# Insight.net
KiCad netlist of a schematic drawn in EAGLE
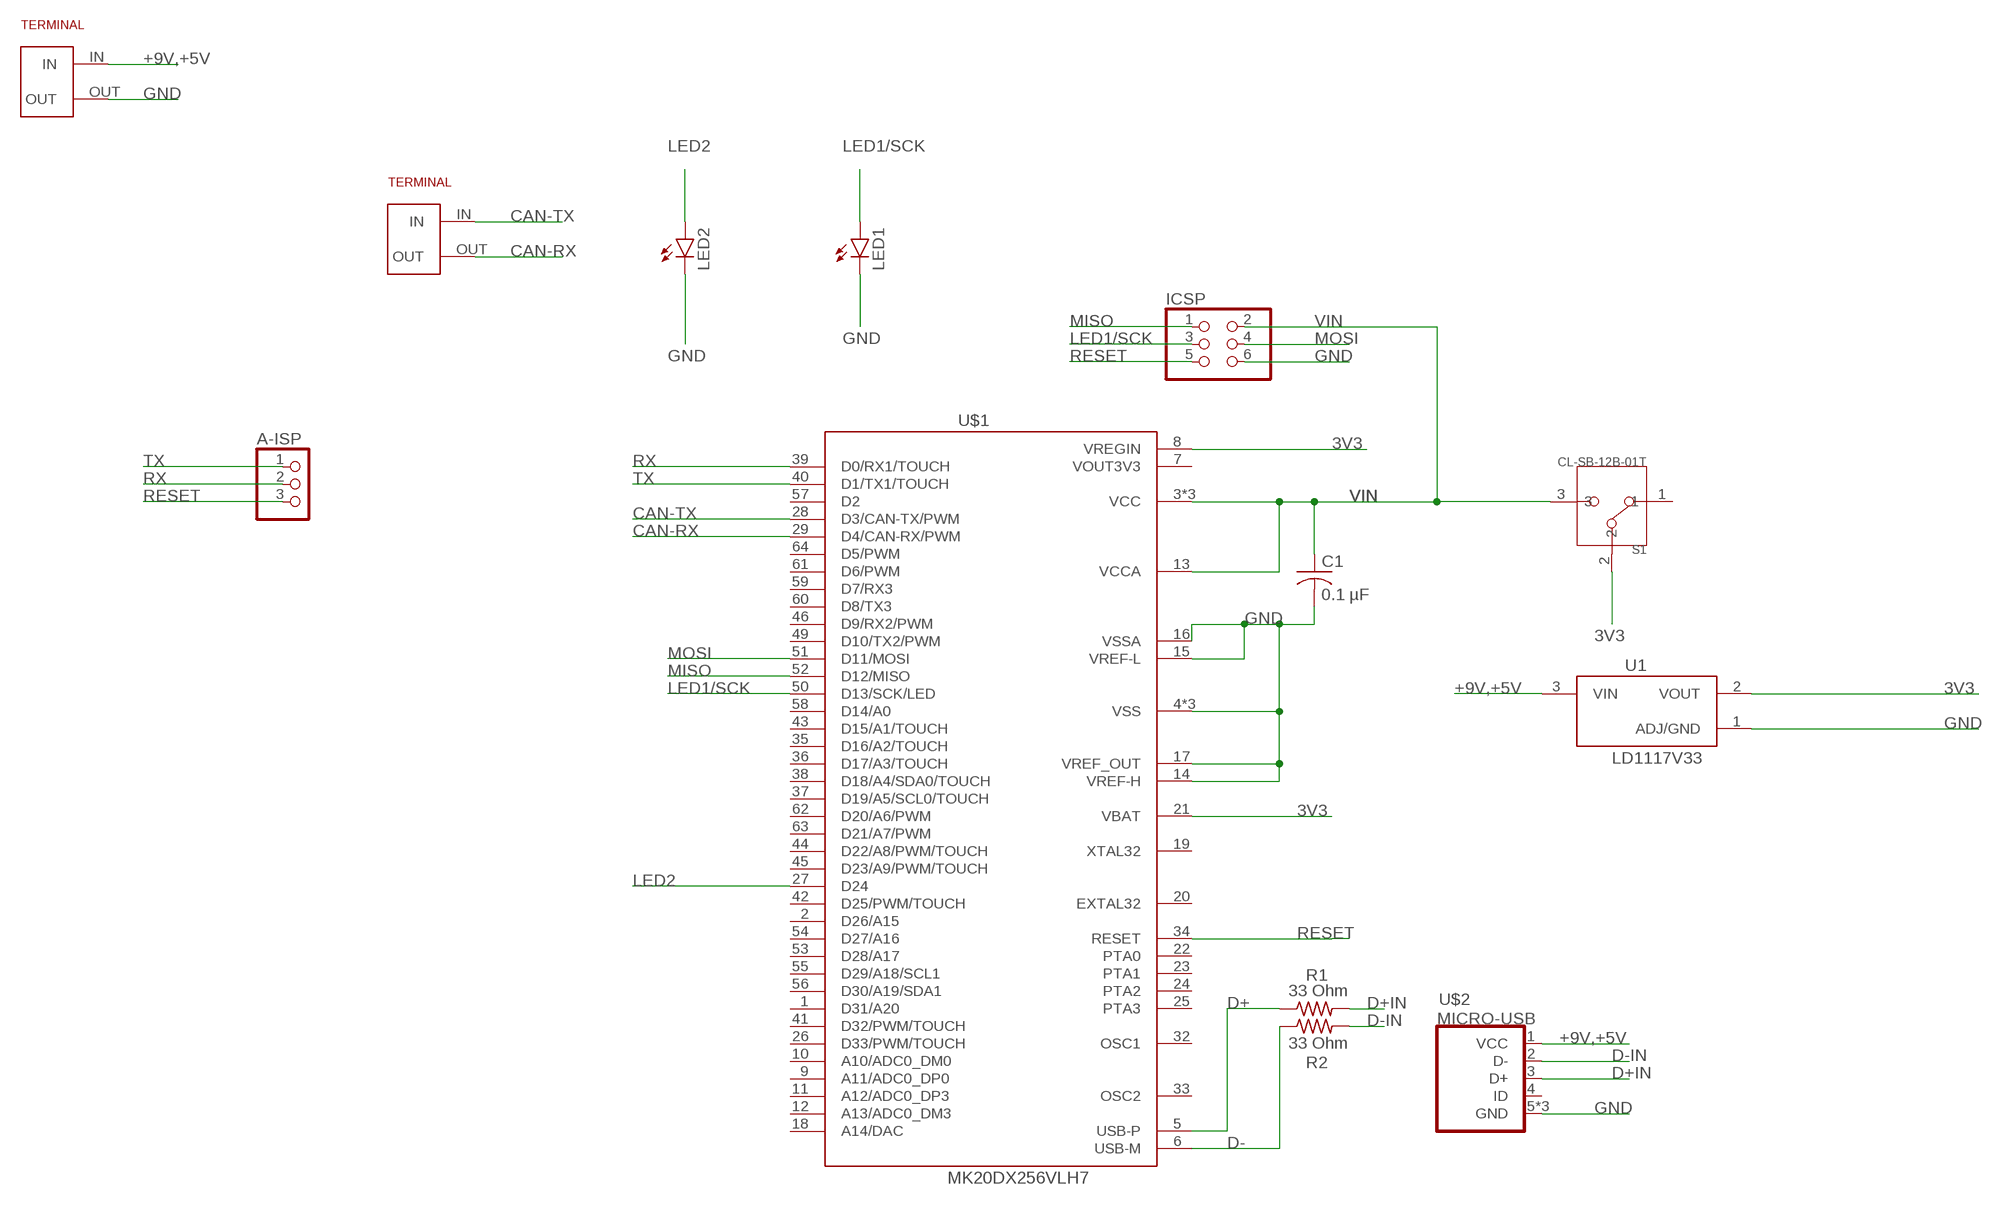
[diagram p0: schematic, sheet 1]

(export (version "E")
  (design (tool "Eeschema 10.0.6"))
  (components
    (comp (ref "A-ISP")
      (value "PINHD-1X3")
      (footprint "eagle-import:1X03")
      (libsource (lib "eagle-import") (part "PINHD-1X3"))
    )
    (comp (ref "C1")
      (value "0.1 µF")
      (footprint "eagle-import:C0805")
      (libsource (lib "eagle-import") (part "C-USC0805"))
    )
    (comp (ref "ICSP")
      (value "PINHD-2X3")
      (footprint "eagle-import:2X03")
      (libsource (lib "eagle-import") (part "PINHD-2X3"))
    )
    (comp (ref "LED1")
      (value "LED5MM")
      (footprint "eagle-import:LED5MM")
      (libsource (lib "eagle-import") (part "LED5MM"))
    )
    (comp (ref "LED2")
      (value "LED5MM")
      (footprint "eagle-import:LED5MM")
      (libsource (lib "eagle-import") (part "LED5MM"))
    )
    (comp (ref "R1")
      (value "33 Ohm")
      (footprint "eagle-import:R1206")
      (libsource (lib "eagle-import") (part "R-US_R1206"))
    )
    (comp (ref "R2")
      (value "33 Ohm")
      (footprint "eagle-import:R1206")
      (libsource (lib "eagle-import") (part "R-US_R1206"))
    )
    (comp (ref "S1")
      (value "CL-SB-12B-01T")
      (footprint "eagle-import:CL-SB-12B")
      (fields (field (name "MF") "Nidec Copal"))
      (libsource (lib "eagle-import") (part "CL-SB-12B-01T"))
    )
    (comp (ref "U$1")
      (value "MK20DX256VLH7")
      (footprint "eagle-import:QFP50P1200X1200X160-64N")
      (fields (field (name "MF") "NXP USA"))
      (libsource (lib "eagle-import") (part "MK20DX256VLH7"))
    )
    (comp (ref "U$2")
      (value "MICRO-USB")
      (footprint "eagle-import:MICRO-USB")
      (libsource (lib "eagle-import") (part "MICRO-USB"))
    )
    (comp (ref "U$3")
      (value "SCREWTERMINAL")
      (footprint "eagle-import:SCREWTERMINAL")
      (libsource (lib "eagle-import") (part "SCREWTERMINAL"))
    )
    (comp (ref "U$4")
      (value "SCREWTERMINAL")
      (footprint "eagle-import:SCREWTERMINAL")
      (libsource (lib "eagle-import") (part "SCREWTERMINAL"))
    )
    (comp (ref "U1")
      (value "LD1117V33")
      (footprint "eagle-import:TO255P1020X450X1968-3")
      (fields (field (name "MF") "STMicroelectronics"))
      (libsource (lib "eagle-import") (part "LD1117V33"))
    )
  )
  (nets
    (net (code "1") (name "/+9V,+5V") (class "Default")
      (node (ref "U$2") (pin "1") (pinfunction "VCC_1") (pintype "power_in"))
      (node (ref "U$3") (pin "IN") (pinfunction "IN_IN") (pintype "bidirectional"))
      (node (ref "U1") (pin "3") (pinfunction "VIN_3") (pintype "input"))
    )
    (net (code "2") (name "/3V3") (class "Default")
      (node (ref "S1") (pin "2") (pinfunction "2_2") (pintype "bidirectional"))
      (node (ref "U$1") (pin "21") (pinfunction "VBAT_21") (pintype "bidirectional"))
      (node (ref "U$1") (pin "8") (pinfunction "VREGIN_8") (pintype "bidirectional"))
      (node (ref "U1") (pin "2") (pinfunction "VOUT_2") (pintype "output"))
    )
    (net (code "3") (name "/CAN-RX") (class "Default")
      (node (ref "U$1") (pin "29") (pinfunction "D4/CAN-RX/PWM_29") (pintype "bidirectional"))
      (node (ref "U$4") (pin "OUT") (pinfunction "OUT_OUT") (pintype "bidirectional"))
    )
    (net (code "4") (name "/CAN-TX") (class "Default")
      (node (ref "U$1") (pin "28") (pinfunction "D3/CAN-TX/PWM_28") (pintype "bidirectional"))
      (node (ref "U$4") (pin "IN") (pinfunction "IN_IN") (pintype "bidirectional"))
    )
    (net (code "5") (name "/D+") (class "Default")
      (node (ref "R1") (pin "1") (pinfunction "1_1") (pintype "passive"))
      (node (ref "U$1") (pin "5") (pinfunction "USB-P_5") (pintype "bidirectional"))
    )
    (net (code "6") (name "/D+IN") (class "Default")
      (node (ref "R1") (pin "2") (pinfunction "2_2") (pintype "passive"))
      (node (ref "U$2") (pin "3") (pinfunction "D+_3") (pintype "bidirectional"))
    )
    (net (code "7") (name "/D-") (class "Default")
      (node (ref "R2") (pin "1") (pinfunction "1_1") (pintype "passive"))
      (node (ref "U$1") (pin "6") (pinfunction "USB-M_6") (pintype "bidirectional"))
    )
    (net (code "8") (name "/D-IN") (class "Default")
      (node (ref "R2") (pin "2") (pinfunction "2_2") (pintype "passive"))
      (node (ref "U$2") (pin "2") (pinfunction "D-_2") (pintype "bidirectional"))
    )
    (net (code "9") (name "/GND") (class "Default")
      (node (ref "C1") (pin "2") (pinfunction "2_2") (pintype "passive"))
      (node (ref "ICSP") (pin "6") (pinfunction "6_6") (pintype "passive"))
      (node (ref "LED1") (pin "K") (pinfunction "C_K") (pintype "passive"))
      (node (ref "LED2") (pin "K") (pinfunction "C_K") (pintype "passive"))
      (node (ref "U$1") (pin "14") (pinfunction "VREF-H_14") (pintype "bidirectional"))
      (node (ref "U$1") (pin "15") (pinfunction "VREF-L_15") (pintype "bidirectional"))
      (node (ref "U$1") (pin "16") (pinfunction "VSSA_16") (pintype "bidirectional"))
      (node (ref "U$1") (pin "17") (pinfunction "VREF_OUT_17") (pintype "bidirectional"))
      (node (ref "U$1") (pin "31") (pinfunction "VSS_31") (pintype "bidirectional"))
      (node (ref "U$1") (pin "4") (pinfunction "VSS_4") (pintype "bidirectional"))
      (node (ref "U$1") (pin "47") (pinfunction "VSS_47") (pintype "bidirectional"))
      (node (ref "U$2") (pin "5") (pinfunction "GND_5") (pintype "power_in"))
      (node (ref "U$2") (pin "GND1") (pinfunction "GND_GND1") (pintype "power_in"))
      (node (ref "U$2") (pin "GND2") (pinfunction "GND_GND2") (pintype "power_in"))
      (node (ref "U$3") (pin "OUT") (pinfunction "OUT_OUT") (pintype "bidirectional"))
      (node (ref "U1") (pin "1") (pinfunction "ADJ/GND_1") (pintype "passive"))
    )
    (net (code "10") (name "/LED1{slash}SCK") (class "Default")
      (node (ref "ICSP") (pin "3") (pinfunction "3_3") (pintype "passive"))
      (node (ref "LED1") (pin "A") (pinfunction "A_A") (pintype "passive"))
      (node (ref "U$1") (pin "50") (pinfunction "D13/SCK/LED_50") (pintype "bidirectional"))
    )
    (net (code "11") (name "/LED2") (class "Default")
      (node (ref "LED2") (pin "A") (pinfunction "A_A") (pintype "passive"))
      (node (ref "U$1") (pin "27") (pinfunction "D24_27") (pintype "bidirectional"))
    )
    (net (code "12") (name "/MISO") (class "Default")
      (node (ref "ICSP") (pin "1") (pinfunction "1_1") (pintype "passive"))
      (node (ref "U$1") (pin "52") (pinfunction "D12/MISO_52") (pintype "bidirectional"))
    )
    (net (code "13") (name "/MOSI") (class "Default")
      (node (ref "ICSP") (pin "4") (pinfunction "4_4") (pintype "passive"))
      (node (ref "U$1") (pin "51") (pinfunction "D11/MOSI_51") (pintype "bidirectional"))
    )
    (net (code "14") (name "/RESET") (class "Default")
      (node (ref "A-ISP") (pin "3") (pinfunction "3_3") (pintype "passive"))
      (node (ref "ICSP") (pin "5") (pinfunction "5_5") (pintype "passive"))
      (node (ref "U$1") (pin "34") (pinfunction "RESET_34") (pintype "bidirectional"))
    )
    (net (code "15") (name "/RX") (class "Default")
      (node (ref "A-ISP") (pin "2") (pinfunction "2_2") (pintype "passive"))
      (node (ref "U$1") (pin "39") (pinfunction "D0/RX1/TOUCH_39") (pintype "bidirectional"))
    )
    (net (code "16") (name "/TX") (class "Default")
      (node (ref "A-ISP") (pin "1") (pinfunction "1_1") (pintype "passive"))
      (node (ref "U$1") (pin "40") (pinfunction "D1/TX1/TOUCH_40") (pintype "bidirectional"))
    )
    (net (code "17") (name "/VIN") (class "Default")
      (node (ref "C1") (pin "1") (pinfunction "1_1") (pintype "passive"))
      (node (ref "ICSP") (pin "2") (pinfunction "2_2") (pintype "passive"))
      (node (ref "S1") (pin "3") (pinfunction "3_3") (pintype "bidirectional"))
      (node (ref "U$1") (pin "13") (pinfunction "VCCA_13") (pintype "bidirectional"))
      (node (ref "U$1") (pin "3") (pinfunction "VCC_3") (pintype "bidirectional"))
      (node (ref "U$1") (pin "30") (pinfunction "VCC_30") (pintype "bidirectional"))
      (node (ref "U$1") (pin "48") (pinfunction "VCC_48") (pintype "bidirectional"))
    )
    (net (code "18") (name "unconnected-(S1-Pad1)") (class "Default")
      (node (ref "S1") (pin "1") (pinfunction "1_1") (pintype "bidirectional"))
    )
    (net (code "19") (name "unconnected-(U$1-A10{slash}ADC0_DM0-Pad10)") (class "Default")
      (node (ref "U$1") (pin "10") (pinfunction "A10/ADC0_DM0_10") (pintype "bidirectional"))
    )
    (net (code "20") (name "unconnected-(U$1-A11{slash}ADC0_DP0-Pad9)") (class "Default")
      (node (ref "U$1") (pin "9") (pinfunction "A11/ADC0_DP0_9") (pintype "bidirectional"))
    )
    (net (code "21") (name "unconnected-(U$1-A12{slash}ADC0_DP3-Pad11)") (class "Default")
      (node (ref "U$1") (pin "11") (pinfunction "A12/ADC0_DP3_11") (pintype "bidirectional"))
    )
    (net (code "22") (name "unconnected-(U$1-A13{slash}ADC0_DM3-Pad12)") (class "Default")
      (node (ref "U$1") (pin "12") (pinfunction "A13/ADC0_DM3_12") (pintype "bidirectional"))
    )
    (net (code "23") (name "unconnected-(U$1-A14{slash}DAC-Pad18)") (class "Default")
      (node (ref "U$1") (pin "18") (pinfunction "A14/DAC_18") (pintype "bidirectional"))
    )
    (net (code "24") (name "unconnected-(U$1-D2-Pad57)") (class "Default")
      (node (ref "U$1") (pin "57") (pinfunction "D2_57") (pintype "bidirectional"))
    )
    (net (code "25") (name "unconnected-(U$1-D5{slash}PWM-Pad64)") (class "Default")
      (node (ref "U$1") (pin "64") (pinfunction "D5/PWM_64") (pintype "bidirectional"))
    )
    (net (code "26") (name "unconnected-(U$1-D6{slash}PWM-Pad61)") (class "Default")
      (node (ref "U$1") (pin "61") (pinfunction "D6/PWM_61") (pintype "bidirectional"))
    )
    (net (code "27") (name "unconnected-(U$1-D7{slash}RX3-Pad59)") (class "Default")
      (node (ref "U$1") (pin "59") (pinfunction "D7/RX3_59") (pintype "bidirectional"))
    )
    (net (code "28") (name "unconnected-(U$1-D8{slash}TX3-Pad60)") (class "Default")
      (node (ref "U$1") (pin "60") (pinfunction "D8/TX3_60") (pintype "bidirectional"))
    )
    (net (code "29") (name "unconnected-(U$1-D9{slash}RX2{slash}PWM-Pad46)") (class "Default")
      (node (ref "U$1") (pin "46") (pinfunction "D9/RX2/PWM_46") (pintype "bidirectional"))
    )
    (net (code "30") (name "unconnected-(U$1-D10{slash}TX2{slash}PWM-Pad49)") (class "Default")
      (node (ref "U$1") (pin "49") (pinfunction "D10/TX2/PWM_49") (pintype "bidirectional"))
    )
    (net (code "31") (name "unconnected-(U$1-D14{slash}A0-Pad58)") (class "Default")
      (node (ref "U$1") (pin "58") (pinfunction "D14/A0_58") (pintype "bidirectional"))
    )
    (net (code "32") (name "unconnected-(U$1-D15{slash}A1{slash}TOUCH-Pad43)") (class "Default")
      (node (ref "U$1") (pin "43") (pinfunction "D15/A1/TOUCH_43") (pintype "bidirectional"))
    )
    (net (code "33") (name "unconnected-(U$1-D16{slash}A2{slash}TOUCH-Pad35)") (class "Default")
      (node (ref "U$1") (pin "35") (pinfunction "D16/A2/TOUCH_35") (pintype "bidirectional"))
    )
    (net (code "34") (name "unconnected-(U$1-D17{slash}A3{slash}TOUCH-Pad36)") (class "Default")
      (node (ref "U$1") (pin "36") (pinfunction "D17/A3/TOUCH_36") (pintype "bidirectional"))
    )
    (net (code "35") (name "unconnected-(U$1-D18{slash}A4{slash}SDA0{slash}TOUCH-Pad38)") (class "Default")
      (node (ref "U$1") (pin "38") (pinfunction "D18/A4/SDA0/TOUCH_38") (pintype "bidirectional"))
    )
    (net (code "36") (name "unconnected-(U$1-D19{slash}A5{slash}SCL0{slash}TOUCH-Pad37)") (class "Default")
      (node (ref "U$1") (pin "37") (pinfunction "D19/A5/SCL0/TOUCH_37") (pintype "bidirectional"))
    )
    (net (code "37") (name "unconnected-(U$1-D20{slash}A6{slash}PWM-Pad62)") (class "Default")
      (node (ref "U$1") (pin "62") (pinfunction "D20/A6/PWM_62") (pintype "bidirectional"))
    )
    (net (code "38") (name "unconnected-(U$1-D21{slash}A7{slash}PWM-Pad63)") (class "Default")
      (node (ref "U$1") (pin "63") (pinfunction "D21/A7/PWM_63") (pintype "bidirectional"))
    )
    (net (code "39") (name "unconnected-(U$1-D22{slash}A8{slash}PWM{slash}TOUCH-Pad44)") (class "Default")
      (node (ref "U$1") (pin "44") (pinfunction "D22/A8/PWM/TOUCH_44") (pintype "bidirectional"))
    )
    (net (code "40") (name "unconnected-(U$1-D23{slash}A9{slash}PWM{slash}TOUCH-Pad45)") (class "Default")
      (node (ref "U$1") (pin "45") (pinfunction "D23/A9/PWM/TOUCH_45") (pintype "bidirectional"))
    )
    (net (code "41") (name "unconnected-(U$1-D25{slash}PWM{slash}TOUCH-Pad42)") (class "Default")
      (node (ref "U$1") (pin "42") (pinfunction "D25/PWM/TOUCH_42") (pintype "bidirectional"))
    )
    (net (code "42") (name "unconnected-(U$1-D26{slash}A15-Pad2)") (class "Default")
      (node (ref "U$1") (pin "2") (pinfunction "D26/A15_2") (pintype "bidirectional"))
    )
    (net (code "43") (name "unconnected-(U$1-D27{slash}A16-Pad54)") (class "Default")
      (node (ref "U$1") (pin "54") (pinfunction "D27/A16_54") (pintype "bidirectional"))
    )
    (net (code "44") (name "unconnected-(U$1-D28{slash}A17-Pad53)") (class "Default")
      (node (ref "U$1") (pin "53") (pinfunction "D28/A17_53") (pintype "bidirectional"))
    )
    (net (code "45") (name "unconnected-(U$1-D29{slash}A18{slash}SCL1-Pad55)") (class "Default")
      (node (ref "U$1") (pin "55") (pinfunction "D29/A18/SCL1_55") (pintype "bidirectional"))
    )
    (net (code "46") (name "unconnected-(U$1-D30{slash}A19{slash}SDA1-Pad56)") (class "Default")
      (node (ref "U$1") (pin "56") (pinfunction "D30/A19/SDA1_56") (pintype "bidirectional"))
    )
    (net (code "47") (name "unconnected-(U$1-D31{slash}A20-Pad1)") (class "Default")
      (node (ref "U$1") (pin "1") (pinfunction "D31/A20_1") (pintype "bidirectional"))
    )
    (net (code "48") (name "unconnected-(U$1-D32{slash}PWM{slash}TOUCH-Pad41)") (class "Default")
      (node (ref "U$1") (pin "41") (pinfunction "D32/PWM/TOUCH_41") (pintype "bidirectional"))
    )
    (net (code "49") (name "unconnected-(U$1-D33{slash}PWM{slash}TOUCH-Pad26)") (class "Default")
      (node (ref "U$1") (pin "26") (pinfunction "D33/PWM/TOUCH_26") (pintype "bidirectional"))
    )
    (net (code "50") (name "unconnected-(U$1-EXTAL32-Pad20)") (class "Default")
      (node (ref "U$1") (pin "20") (pinfunction "EXTAL32_20") (pintype "bidirectional"))
    )
    (net (code "51") (name "unconnected-(U$1-OSC1-Pad32)") (class "Default")
      (node (ref "U$1") (pin "32") (pinfunction "OSC1_32") (pintype "bidirectional"))
    )
    (net (code "52") (name "unconnected-(U$1-OSC2-Pad33)") (class "Default")
      (node (ref "U$1") (pin "33") (pinfunction "OSC2_33") (pintype "bidirectional"))
    )
    (net (code "53") (name "unconnected-(U$1-PTA0-Pad22)") (class "Default")
      (node (ref "U$1") (pin "22") (pinfunction "PTA0_22") (pintype "bidirectional"))
    )
    (net (code "54") (name "unconnected-(U$1-PTA1-Pad23)") (class "Default")
      (node (ref "U$1") (pin "23") (pinfunction "PTA1_23") (pintype "bidirectional"))
    )
    (net (code "55") (name "unconnected-(U$1-PTA2-Pad24)") (class "Default")
      (node (ref "U$1") (pin "24") (pinfunction "PTA2_24") (pintype "bidirectional"))
    )
    (net (code "56") (name "unconnected-(U$1-PTA3-Pad25)") (class "Default")
      (node (ref "U$1") (pin "25") (pinfunction "PTA3_25") (pintype "bidirectional"))
    )
    (net (code "57") (name "unconnected-(U$1-VOUT3V3-Pad7)") (class "Default")
      (node (ref "U$1") (pin "7") (pinfunction "VOUT3V3_7") (pintype "bidirectional"))
    )
    (net (code "58") (name "unconnected-(U$1-XTAL32-Pad19)") (class "Default")
      (node (ref "U$1") (pin "19") (pinfunction "XTAL32_19") (pintype "bidirectional"))
    )
    (net (code "59") (name "unconnected-(U$2-ID-Pad4)") (class "Default")
      (node (ref "U$2") (pin "4") (pinfunction "ID_4") (pintype "bidirectional"))
    )
  )
)
